# working.net
KiCad netlist of a schematic drawn in EAGLE
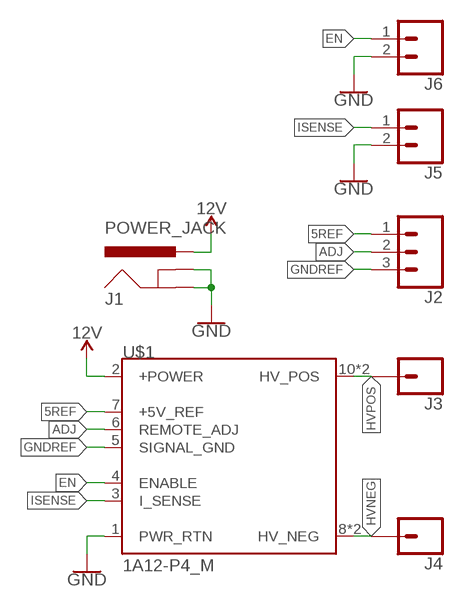
[diagram p0: schematic, sheet 1]

(export (version "E")
  (design (tool "Eeschema 10.0.6"))
  (components
    (comp (ref "J1")
      (value "POWER_JACK")
      (footprint "eagle-import:POWER_JACK_PTH")
      (libsource (lib "eagle-import") (part "POWER_JACK"))
    )
    (comp (ref "J2")
      (value "CONN_031X03_NO_SILK")
      (footprint "eagle-import:1X03_NO_SILK")
      (libsource (lib "eagle-import") (part "CONN_031X03_NO_SILK"))
    )
    (comp (ref "J3")
      (value "CONN_01PTH_2MM")
      (footprint "eagle-import:1X01_2MM")
      (libsource (lib "eagle-import") (part "CONN_01PTH_2MM"))
    )
    (comp (ref "J4")
      (value "CONN_01PTH_2MM")
      (footprint "eagle-import:1X01_2MM")
      (libsource (lib "eagle-import") (part "CONN_01PTH_2MM"))
    )
    (comp (ref "J5")
      (value "CONN_021X02_NO_SILK")
      (footprint "eagle-import:1X02_NO_SILK")
      (libsource (lib "eagle-import") (part "CONN_021X02_NO_SILK"))
    )
    (comp (ref "J6")
      (value "CONN_021X02_NO_SILK")
      (footprint "eagle-import:1X02_NO_SILK")
      (libsource (lib "eagle-import") (part "CONN_021X02_NO_SILK"))
    )
    (comp (ref "U$1")
      (value "1A12-P4_M")
      (footprint "eagle-import:ULTRAVOLT")
      (libsource (lib "eagle-import") (part "1A12-P4_M"))
    )
  )
  (nets
    (net (code "1") (name "5REF") (class "Default")
      (node (ref "J2") (pin "1") (pinfunction "1_1") (pintype "passive"))
      (node (ref "U$1") (pin "7") (pinfunction "+5V_REF_7") (pintype "bidirectional"))
    )
    (net (code "2") (name "12V") (class "Default")
      (node (ref "J1") (pin "PWR") (pinfunction "PWR_PWR") (pintype "bidirectional"))
      (node (ref "U$1") (pin "2") (pinfunction "+POWER_2") (pintype "bidirectional"))
    )
    (net (code "3") (name "ADJ") (class "Default")
      (node (ref "J2") (pin "2") (pinfunction "2_2") (pintype "passive"))
      (node (ref "U$1") (pin "6") (pinfunction "REMOTE_ADJ_6") (pintype "bidirectional"))
    )
    (net (code "4") (name "EN") (class "Default")
      (node (ref "J6") (pin "1") (pinfunction "1_1") (pintype "passive"))
      (node (ref "U$1") (pin "4") (pinfunction "ENABLE_4") (pintype "bidirectional"))
    )
    (net (code "5") (name "GND") (class "Default")
      (node (ref "J1") (pin "GND") (pinfunction "GND_GND") (pintype "bidirectional"))
      (node (ref "J1") (pin "GNDBREAK") (pinfunction "GNDBREAK_GNDBREAK") (pintype "bidirectional"))
      (node (ref "J5") (pin "2") (pinfunction "2_2") (pintype "passive"))
      (node (ref "J6") (pin "2") (pinfunction "2_2") (pintype "passive"))
      (node (ref "U$1") (pin "1") (pinfunction "PWR_RTN_1") (pintype "bidirectional"))
    )
    (net (code "6") (name "GNDREF") (class "Default")
      (node (ref "J2") (pin "3") (pinfunction "3_3") (pintype "passive"))
      (node (ref "U$1") (pin "5") (pinfunction "SIGNAL_GND_5") (pintype "bidirectional"))
    )
    (net (code "7") (name "HVNEG") (class "Default")
      (node (ref "J4") (pin "1") (pinfunction "1_1") (pintype "passive"))
      (node (ref "U$1") (pin "8") (pinfunction "HV_NEG_8") (pintype "bidirectional"))
      (node (ref "U$1") (pin "9") (pinfunction "HV_NEG_9") (pintype "bidirectional"))
    )
    (net (code "8") (name "HVPOS") (class "Default")
      (node (ref "J3") (pin "1") (pinfunction "1_1") (pintype "passive"))
      (node (ref "U$1") (pin "10") (pinfunction "HV_POS_10") (pintype "bidirectional"))
      (node (ref "U$1") (pin "11") (pinfunction "HV_POS_11") (pintype "bidirectional"))
    )
    (net (code "9") (name "ISENSE") (class "Default")
      (node (ref "J5") (pin "1") (pinfunction "1_1") (pintype "passive"))
      (node (ref "U$1") (pin "3") (pinfunction "I_SENSE_3") (pintype "bidirectional"))
    )
  )
)
